# NakujaN2.net
KiCad netlist of a schematic drawn in EasyEDA
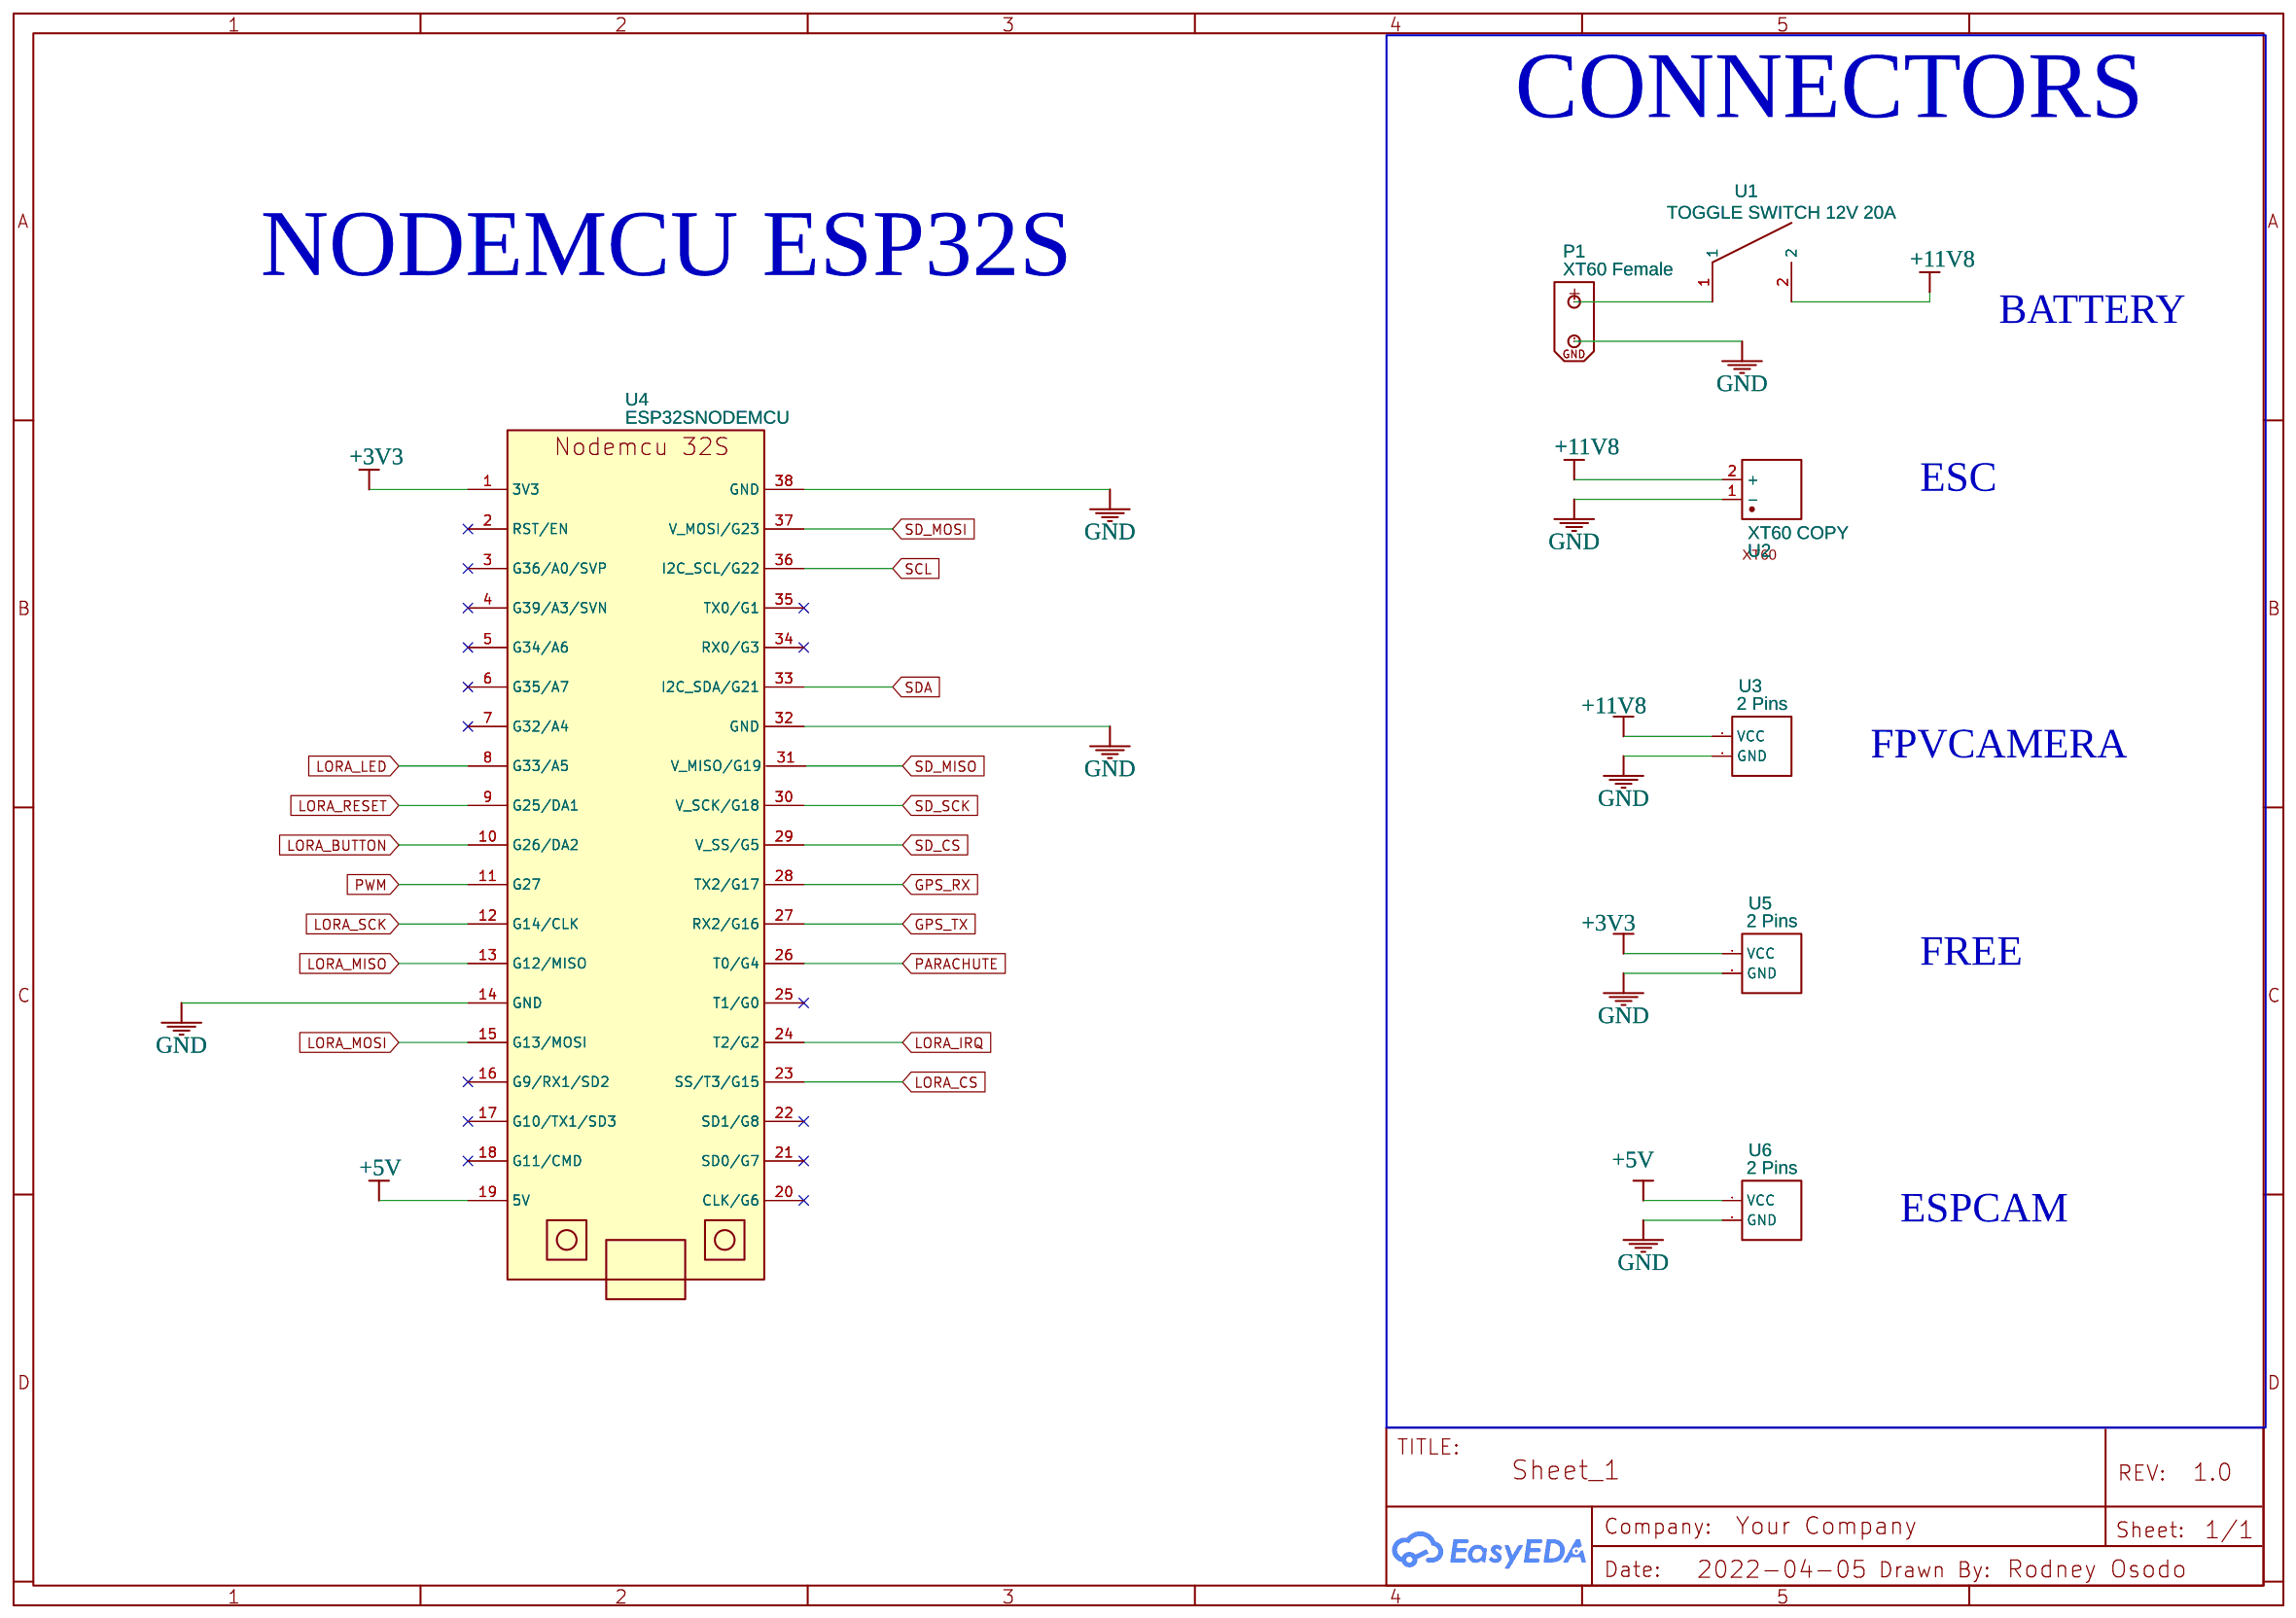
[diagram p0: ESP]
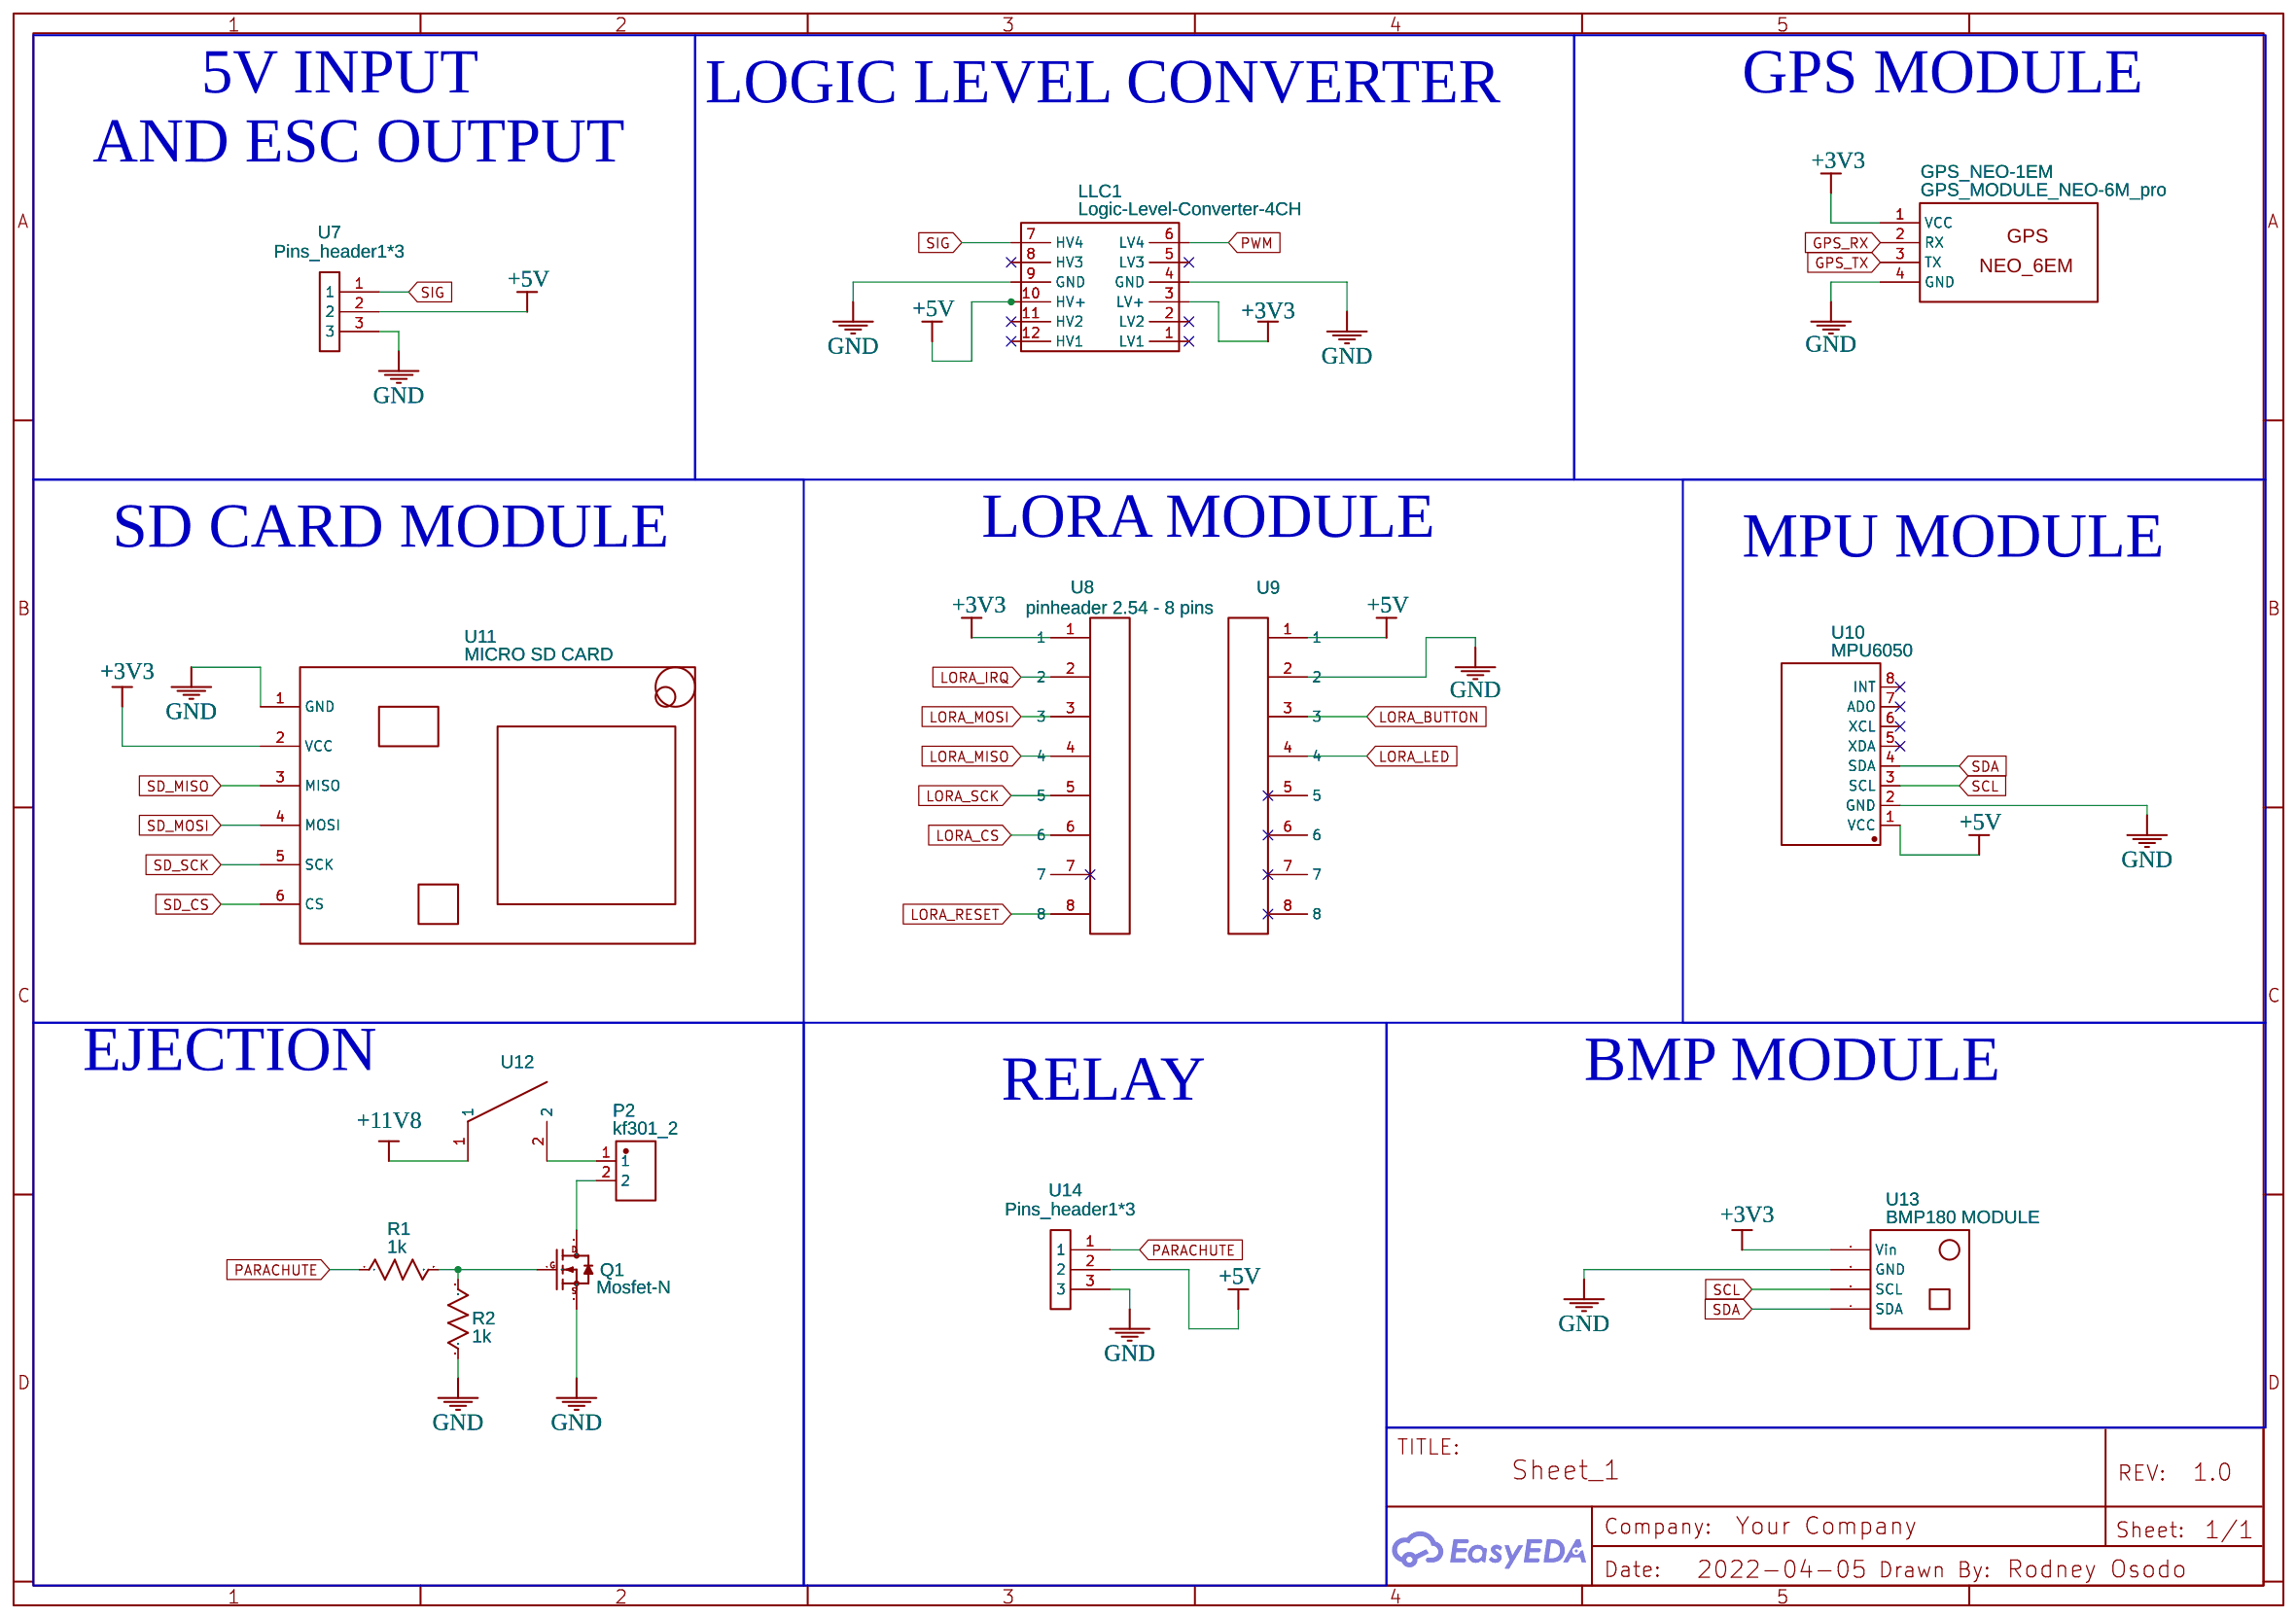
[diagram p1: SENSORS]

(export (version "E")
  (design (tool "Eeschema 10.0.6"))
  (components
    (comp (ref "P1")
      (value "XT60 Female")
      (fields (field (name "BOM_Manufacturer Part") "XT60-F"))
      (libsource (lib "") (part "XT60 Female"))
    )
    (comp (ref "U1") (value "TOGGLE SWITCH 12V 20A") (libsource (lib "") (part "TOGGLE SWITCH 12V 20A")))
    (comp (ref "U2") (value "XT60 COPY") (libsource (lib "") (part "XT60 COPY")))
    (comp (ref "U3") (value "2 Pins") (libsource (lib "") (part "2 Pins")))
    (comp (ref "U4")
      (value "ESP32SNODEMCU")
      (fields (field (name "BOM_Manufacturer Part") "Nodemcu esp32"))
      (libsource (lib "") (part "ESP32SNODEMCU"))
    )
    (comp (ref "U5") (value "2 Pins") (libsource (lib "") (part "2 Pins")))
    (comp (ref "U6") (value "2 Pins") (libsource (lib "") (part "2 Pins")))
    (comp (ref "GPS_NEO-1EM")
      (value "GPS_MODULE_NEO-6M_pro")
      (libsource (lib "") (part "GPS_MODULE_NEO-6M_pro"))
    )
    (comp (ref "LLC1")
      (value "Logic-Level-Converter-4CH")
      (fields (field (name "BOM_Supplier Part") "50807"))
      (libsource (lib "") (part "Logic-Level-Converter-4CH"))
    )
    (comp (ref "P2")
      (value "kf301_2")
      (fields (field (name "BOM_Supplier Part") "C33435"))
      (libsource (lib "") (part "kf301_2"))
    )
    (comp (ref "Q1") (value "Mosfet-N") (libsource (lib "") (part "Mosfet-N")))
    (comp (ref "R1") (value "1k") (libsource (lib "") (part "R_AXIAL-0.6_US_1")))
    (comp (ref "R2") (value "1k") (libsource (lib "") (part "R_AXIAL-0.6_US")))
    (comp (ref "U7") (value "Pins_header1*3") (libsource (lib "") (part "Pins_header1*3")))
    (comp (ref "U8") (value "pinheader 2.54 - 8 pins") (libsource (lib "") (part "pinheader 2.54 - 8 pins")))
    (comp (ref "U9")
      (value "pinheader 2.54 - 8 pins")
      (libsource (lib "") (part "pinheader 2.54 - 8 pins_1"))
    )
    (comp (ref "U10")
      (value "MPU6050")
      (fields (field (name "BOM_Supplier Part") "GY521"))
      (libsource (lib "") (part "MPU6050"))
    )
    (comp (ref "U11") (value "MICRO SD CARD") (libsource (lib "") (part "MICRO SD CARD")))
    (comp (ref "U12") (value "TOGGLE SWITCH 12V 20A") (libsource (lib "") (part "TOGGLE SWITCH 12V 20A")))
    (comp (ref "U13")
      (value "BMP180 MODULE")
      (fields (field (name "BOM_Manufacturer Part") "BMP180 (HW-596)"))
      (libsource (lib "") (part "BMP180 MODULE"))
    )
    (comp (ref "U14") (value "Pins_header1*3") (libsource (lib "") (part "Pins_header1*3")))
  )
  (nets
    (net (code "1") (name "+3V3") (class "Default")
      (node (ref "GPS_NEO-1EM") (pin "1") (pinfunction "VCC_1") (pintype "passive"))
      (node (ref "LLC1") (pin "3") (pinfunction "LV+_3") (pintype "unspecified"))
      (node (ref "U11") (pin "2") (pinfunction "VCC_2") (pintype "unspecified"))
      (node (ref "U13") (pin "1") (pinfunction "Vin_1") (pintype "unspecified"))
      (node (ref "U4") (pin "1") (pinfunction "3V3_1") (pintype "passive"))
      (node (ref "U5") (pin "1") (pinfunction "VCC_1") (pintype "unspecified"))
      (node (ref "U8") (pin "1") (pinfunction "1_1") (pintype "unspecified"))
    )
    (net (code "2") (name "+5V") (class "Default")
      (node (ref "LLC1") (pin "10") (pinfunction "HV+_10") (pintype "unspecified"))
      (node (ref "U10") (pin "1") (pinfunction "VCC_1") (pintype "unspecified"))
      (node (ref "U14") (pin "2") (pinfunction "2_2") (pintype "unspecified"))
      (node (ref "U4") (pin "19") (pinfunction "5V_19") (pintype "passive"))
      (node (ref "U6") (pin "1") (pinfunction "VCC_1") (pintype "unspecified"))
      (node (ref "U7") (pin "2") (pinfunction "2_2") (pintype "unspecified"))
      (node (ref "U9") (pin "1") (pinfunction "1_1") (pintype "unspecified"))
    )
    (net (code "3") (name "+11V8") (class "Default")
      (node (ref "U1") (pin "2") (pinfunction "2_2") (pintype "unspecified"))
      (node (ref "U12") (pin "1") (pinfunction "1_1") (pintype "unspecified"))
      (node (ref "U2") (pin "2") (pinfunction "+_2") (pintype "unspecified"))
      (node (ref "U3") (pin "1") (pinfunction "VCC_1") (pintype "unspecified"))
    )
    (net (code "4") (name "GND") (class "Default")
      (node (ref "GPS_NEO-1EM") (pin "4") (pinfunction "GND_4") (pintype "passive"))
      (node (ref "LLC1") (pin "4") (pinfunction "GND_4") (pintype "unspecified"))
      (node (ref "LLC1") (pin "9") (pinfunction "GND_9") (pintype "unspecified"))
      (node (ref "P1") (pin "1") (pinfunction "1_1") (pintype "unspecified"))
      (node (ref "Q1") (pin "3") (pinfunction "S_3") (pintype "unspecified"))
      (node (ref "R2") (pin "1") (pinfunction "1_1") (pintype "unspecified"))
      (node (ref "U10") (pin "2") (pinfunction "GND_2") (pintype "unspecified"))
      (node (ref "U11") (pin "1") (pinfunction "GND_1") (pintype "unspecified"))
      (node (ref "U13") (pin "2") (pinfunction "GND_2") (pintype "unspecified"))
      (node (ref "U14") (pin "3") (pinfunction "3_3") (pintype "unspecified"))
      (node (ref "U2") (pin "1") (pinfunction "-_1") (pintype "unspecified"))
      (node (ref "U3") (pin "2") (pinfunction "GND_2") (pintype "unspecified"))
      (node (ref "U4") (pin "14") (pinfunction "GND_14") (pintype "passive"))
      (node (ref "U4") (pin "32") (pinfunction "GND_32") (pintype "passive"))
      (node (ref "U4") (pin "38") (pinfunction "GND_38") (pintype "passive"))
      (node (ref "U5") (pin "2") (pinfunction "GND_2") (pintype "unspecified"))
      (node (ref "U6") (pin "2") (pinfunction "GND_2") (pintype "unspecified"))
      (node (ref "U7") (pin "3") (pinfunction "3_3") (pintype "unspecified"))
      (node (ref "U9") (pin "2") (pinfunction "2_2") (pintype "unspecified"))
    )
    (net (code "5") (name "GPS_RX") (class "Default")
      (node (ref "GPS_NEO-1EM") (pin "2") (pinfunction "RX_2") (pintype "input"))
      (node (ref "U4") (pin "28") (pinfunction "TX2/G17_28") (pintype "bidirectional"))
    )
    (net (code "6") (name "GPS_TX") (class "Default")
      (node (ref "GPS_NEO-1EM") (pin "3") (pinfunction "TX_3") (pintype "output"))
      (node (ref "U4") (pin "27") (pinfunction "RX2/G16_27") (pintype "bidirectional"))
    )
    (net (code "7") (name "LORA_BUTTON") (class "Default")
      (node (ref "U4") (pin "10") (pinfunction "G26/DA2_10") (pintype "bidirectional"))
      (node (ref "U9") (pin "3") (pinfunction "3_3") (pintype "unspecified"))
    )
    (net (code "8") (name "LORA_CS") (class "Default")
      (node (ref "U4") (pin "23") (pinfunction "SS/T3/G15_23") (pintype "bidirectional"))
      (node (ref "U8") (pin "6") (pinfunction "6_6") (pintype "unspecified"))
    )
    (net (code "9") (name "LORA_IRQ") (class "Default")
      (node (ref "U4") (pin "24") (pinfunction "T2/G2_24") (pintype "bidirectional"))
      (node (ref "U8") (pin "2") (pinfunction "2_2") (pintype "unspecified"))
    )
    (net (code "10") (name "LORA_LED") (class "Default")
      (node (ref "U4") (pin "8") (pinfunction "G33/A5_8") (pintype "bidirectional"))
      (node (ref "U9") (pin "4") (pinfunction "4_4") (pintype "unspecified"))
    )
    (net (code "11") (name "LORA_MISO") (class "Default")
      (node (ref "U4") (pin "13") (pinfunction "G12/MISO_13") (pintype "bidirectional"))
      (node (ref "U8") (pin "4") (pinfunction "4_4") (pintype "unspecified"))
    )
    (net (code "12") (name "LORA_MOSI") (class "Default")
      (node (ref "U4") (pin "15") (pinfunction "G13/MOSI_15") (pintype "bidirectional"))
      (node (ref "U8") (pin "3") (pinfunction "3_3") (pintype "unspecified"))
    )
    (net (code "13") (name "LORA_RESET") (class "Default")
      (node (ref "U4") (pin "9") (pinfunction "G25/DA1_9") (pintype "bidirectional"))
      (node (ref "U8") (pin "8") (pinfunction "8_8") (pintype "unspecified"))
    )
    (net (code "14") (name "LORA_SCK") (class "Default")
      (node (ref "U4") (pin "12") (pinfunction "G14/CLK_12") (pintype "bidirectional"))
      (node (ref "U8") (pin "5") (pinfunction "5_5") (pintype "unspecified"))
    )
    (net (code "15") (name "Net-(P1-Pad2)") (class "Default")
      (node (ref "P1") (pin "2") (pinfunction "2_2") (pintype "unspecified"))
      (node (ref "U1") (pin "1") (pinfunction "1_1") (pintype "unspecified"))
    )
    (net (code "16") (name "Net-(P2-Pad1)") (class "Default")
      (node (ref "P2") (pin "1") (pinfunction "1_1") (pintype "unspecified"))
      (node (ref "U12") (pin "2") (pinfunction "2_2") (pintype "unspecified"))
    )
    (net (code "17") (name "Net-(Q1-D)") (class "Default")
      (node (ref "P2") (pin "2") (pinfunction "2_2") (pintype "unspecified"))
      (node (ref "Q1") (pin "2") (pinfunction "D_2") (pintype "unspecified"))
    )
    (net (code "18") (name "Net-(Q1-G)") (class "Default")
      (node (ref "Q1") (pin "1") (pinfunction "G_1") (pintype "unspecified"))
      (node (ref "R1") (pin "2") (pinfunction "2_2") (pintype "unspecified"))
      (node (ref "R2") (pin "2") (pinfunction "2_2") (pintype "unspecified"))
    )
    (net (code "19") (name "PARACHUTE") (class "Default")
      (node (ref "R1") (pin "1") (pinfunction "1_1") (pintype "unspecified"))
      (node (ref "U14") (pin "1") (pinfunction "1_1") (pintype "unspecified"))
      (node (ref "U4") (pin "26") (pinfunction "T0/G4_26") (pintype "bidirectional"))
    )
    (net (code "20") (name "PWM") (class "Default")
      (node (ref "LLC1") (pin "6") (pinfunction "LV4_6") (pintype "unspecified"))
      (node (ref "U4") (pin "11") (pinfunction "G27_11") (pintype "bidirectional"))
    )
    (net (code "21") (name "SCL") (class "Default")
      (node (ref "U10") (pin "3") (pinfunction "SCL_3") (pintype "unspecified"))
      (node (ref "U13") (pin "3") (pinfunction "SCL_3") (pintype "unspecified"))
      (node (ref "U4") (pin "36") (pinfunction "I2C_SCL/G22_36") (pintype "bidirectional"))
    )
    (net (code "22") (name "SDA") (class "Default")
      (node (ref "U10") (pin "4") (pinfunction "SDA_4") (pintype "unspecified"))
      (node (ref "U13") (pin "4") (pinfunction "SDA_4") (pintype "unspecified"))
      (node (ref "U4") (pin "33") (pinfunction "I2C_SDA/G21_33") (pintype "bidirectional"))
    )
    (net (code "23") (name "SD_CS") (class "Default")
      (node (ref "U11") (pin "6") (pinfunction "CS_6") (pintype "unspecified"))
      (node (ref "U4") (pin "29") (pinfunction "V_SS/G5_29") (pintype "bidirectional"))
    )
    (net (code "24") (name "SD_MISO") (class "Default")
      (node (ref "U11") (pin "3") (pinfunction "MISO_3") (pintype "unspecified"))
      (node (ref "U4") (pin "31") (pinfunction "V_MISO/G19_31") (pintype "bidirectional"))
    )
    (net (code "25") (name "SD_MOSI") (class "Default")
      (node (ref "U11") (pin "4") (pinfunction "MOSI_4") (pintype "unspecified"))
      (node (ref "U4") (pin "37") (pinfunction "V_MOSI/G23_37") (pintype "bidirectional"))
    )
    (net (code "26") (name "SD_SCK") (class "Default")
      (node (ref "U11") (pin "5") (pinfunction "SCK_5") (pintype "unspecified"))
      (node (ref "U4") (pin "30") (pinfunction "V_SCK/G18_30") (pintype "bidirectional"))
    )
    (net (code "27") (name "SIG") (class "Default")
      (node (ref "LLC1") (pin "7") (pinfunction "HV4_7") (pintype "unspecified"))
      (node (ref "U7") (pin "1") (pinfunction "1_1") (pintype "unspecified"))
    )
    (net (code "28") (name "unconnected-(LLC1-HV1-Pad12)") (class "Default")
      (node (ref "LLC1") (pin "12") (pinfunction "HV1_12") (pintype "unspecified+no_connect"))
    )
    (net (code "29") (name "unconnected-(LLC1-HV2-Pad11)") (class "Default")
      (node (ref "LLC1") (pin "11") (pinfunction "HV2_11") (pintype "unspecified+no_connect"))
    )
    (net (code "30") (name "unconnected-(LLC1-HV3-Pad8)") (class "Default")
      (node (ref "LLC1") (pin "8") (pinfunction "HV3_8") (pintype "unspecified+no_connect"))
    )
    (net (code "31") (name "unconnected-(LLC1-LV1-Pad1)") (class "Default")
      (node (ref "LLC1") (pin "1") (pinfunction "LV1_1") (pintype "unspecified+no_connect"))
    )
    (net (code "32") (name "unconnected-(LLC1-LV2-Pad2)") (class "Default")
      (node (ref "LLC1") (pin "2") (pinfunction "LV2_2") (pintype "unspecified+no_connect"))
    )
    (net (code "33") (name "unconnected-(LLC1-LV3-Pad5)") (class "Default")
      (node (ref "LLC1") (pin "5") (pinfunction "LV3_5") (pintype "unspecified+no_connect"))
    )
    (net (code "34") (name "unconnected-(U4-CLK{slash}G6-Pad20)") (class "Default")
      (node (ref "U4") (pin "20") (pinfunction "CLK/G6_20") (pintype "bidirectional+no_connect"))
    )
    (net (code "35") (name "unconnected-(U4-G9{slash}RX1{slash}SD2-Pad16)") (class "Default")
      (node (ref "U4") (pin "16") (pinfunction "G9/RX1/SD2_16") (pintype "bidirectional+no_connect"))
    )
    (net (code "36") (name "unconnected-(U4-G10{slash}TX1{slash}SD3-Pad17)") (class "Default")
      (node (ref "U4") (pin "17") (pinfunction "G10/TX1/SD3_17") (pintype "bidirectional+no_connect"))
    )
    (net (code "37") (name "unconnected-(U4-G11{slash}CMD-Pad18)") (class "Default")
      (node (ref "U4") (pin "18") (pinfunction "G11/CMD_18") (pintype "bidirectional+no_connect"))
    )
    (net (code "38") (name "unconnected-(U4-G32{slash}A4-Pad7)") (class "Default")
      (node (ref "U4") (pin "7") (pinfunction "G32/A4_7") (pintype "bidirectional+no_connect"))
    )
    (net (code "39") (name "unconnected-(U4-G34{slash}A6-Pad5)") (class "Default")
      (node (ref "U4") (pin "5") (pinfunction "G34/A6_5") (pintype "bidirectional+no_connect"))
    )
    (net (code "40") (name "unconnected-(U4-G35{slash}A7-Pad6)") (class "Default")
      (node (ref "U4") (pin "6") (pinfunction "G35/A7_6") (pintype "bidirectional+no_connect"))
    )
    (net (code "41") (name "unconnected-(U4-G36{slash}A0{slash}SVP-Pad3)") (class "Default")
      (node (ref "U4") (pin "3") (pinfunction "G36/A0/SVP_3") (pintype "bidirectional+no_connect"))
    )
    (net (code "42") (name "unconnected-(U4-G39{slash}A3{slash}SVN-Pad4)") (class "Default")
      (node (ref "U4") (pin "4") (pinfunction "G39/A3/SVN_4") (pintype "bidirectional+no_connect"))
    )
    (net (code "43") (name "unconnected-(U4-RST{slash}EN-Pad2)") (class "Default")
      (node (ref "U4") (pin "2") (pinfunction "RST/EN_2") (pintype "bidirectional+no_connect"))
    )
    (net (code "44") (name "unconnected-(U4-RX0{slash}G3-Pad34)") (class "Default")
      (node (ref "U4") (pin "34") (pinfunction "RX0/G3_34") (pintype "bidirectional+no_connect"))
    )
    (net (code "45") (name "unconnected-(U4-SD0{slash}G7-Pad21)") (class "Default")
      (node (ref "U4") (pin "21") (pinfunction "SD0/G7_21") (pintype "bidirectional+no_connect"))
    )
    (net (code "46") (name "unconnected-(U4-SD1{slash}G8-Pad22)") (class "Default")
      (node (ref "U4") (pin "22") (pinfunction "SD1/G8_22") (pintype "bidirectional+no_connect"))
    )
    (net (code "47") (name "unconnected-(U4-T1{slash}G0-Pad25)") (class "Default")
      (node (ref "U4") (pin "25") (pinfunction "T1/G0_25") (pintype "bidirectional+no_connect"))
    )
    (net (code "48") (name "unconnected-(U4-TX0{slash}G1-Pad35)") (class "Default")
      (node (ref "U4") (pin "35") (pinfunction "TX0/G1_35") (pintype "bidirectional+no_connect"))
    )
    (net (code "49") (name "unconnected-(U8-Pad7)") (class "Default")
      (node (ref "U8") (pin "7") (pinfunction "7_7") (pintype "unspecified+no_connect"))
    )
    (net (code "50") (name "unconnected-(U9-Pad5)") (class "Default")
      (node (ref "U9") (pin "5") (pinfunction "5_5") (pintype "unspecified+no_connect"))
    )
    (net (code "51") (name "unconnected-(U9-Pad6)") (class "Default")
      (node (ref "U9") (pin "6") (pinfunction "6_6") (pintype "unspecified+no_connect"))
    )
    (net (code "52") (name "unconnected-(U9-Pad7)") (class "Default")
      (node (ref "U9") (pin "7") (pinfunction "7_7") (pintype "unspecified+no_connect"))
    )
    (net (code "53") (name "unconnected-(U9-Pad8)") (class "Default")
      (node (ref "U9") (pin "8") (pinfunction "8_8") (pintype "unspecified+no_connect"))
    )
    (net (code "54") (name "unconnected-(U10-ADO-Pad7)") (class "Default")
      (node (ref "U10") (pin "7") (pinfunction "ADO_7") (pintype "unspecified+no_connect"))
    )
    (net (code "55") (name "unconnected-(U10-INT-Pad8)") (class "Default")
      (node (ref "U10") (pin "8") (pinfunction "INT_8") (pintype "unspecified+no_connect"))
    )
    (net (code "56") (name "unconnected-(U10-XCL-Pad6)") (class "Default")
      (node (ref "U10") (pin "6") (pinfunction "XCL_6") (pintype "unspecified+no_connect"))
    )
    (net (code "57") (name "unconnected-(U10-XDA-Pad5)") (class "Default")
      (node (ref "U10") (pin "5") (pinfunction "XDA_5") (pintype "unspecified+no_connect"))
    )
  )
)
